# 0-WeightSensor.net
KiCad netlist of a schematic drawn in Altium Designer
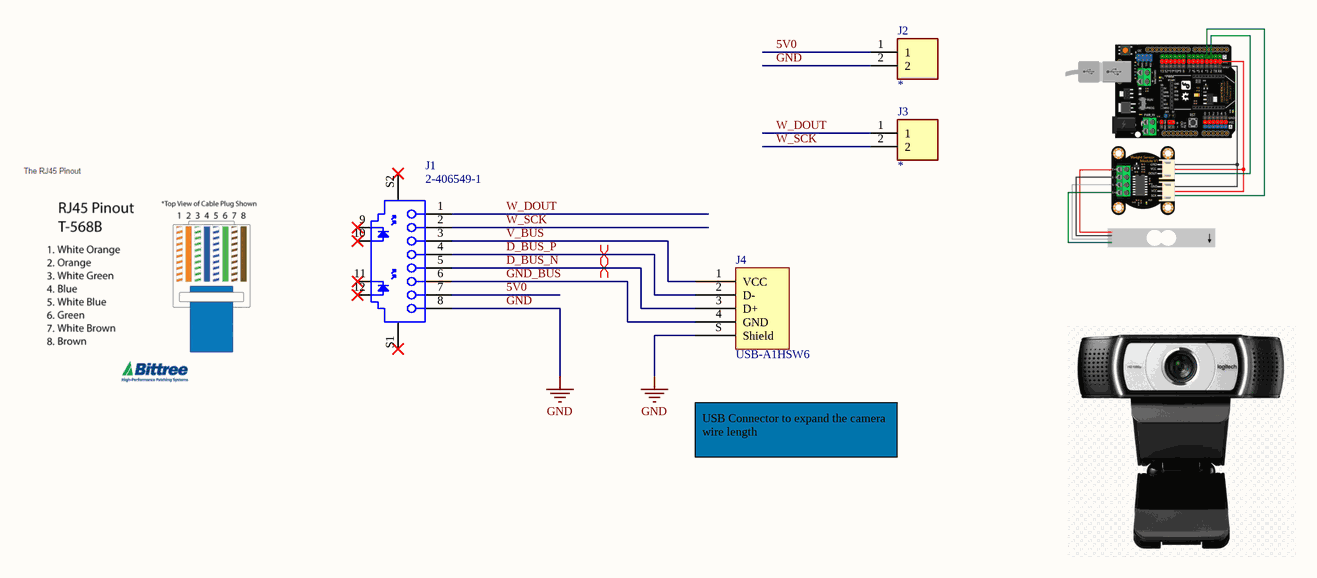
[diagram p0: 0-WeightSensor.SchDoc]

(export (version "E")
  (design (tool "Eeschema 10.0.6"))
  (components
    (comp (ref "J1")
      (value "2-406549-1")
      (footprint "TECO-2-406549-1_V")
      (description "RJ45 Connector, Pitch 1.016 mm, 8 Position, Height 14.22 mm, Tail Length 3.18 mm, RoHS, Tray")
      (fields (field (name "MANUFACTURER") "TE Connectivity"))
      (libsource (lib "Altium Content Vault") (part "RJ45-12-2SHLD_A"))
    )
    (comp (ref "J2")
      (value "282841-2")
      (footprint "TE_282841-2")
      (description "Conn Terminal Block 2 POS 5.08mm Solder ST Thru-Hole 17.5A/Contact")
      (fields (field (name "MF") "TE Connectivity") (field (name "COMMENT_1") "*"))
      (libsource (lib "PTR500-2") (part "282841-2"))
    )
    (comp (ref "J3")
      (value "282841-2")
      (footprint "TE_282841-2")
      (description "Conn Terminal Block 2 POS 5.08mm Solder ST Thru-Hole 17.5A/Contact")
      (fields (field (name "MF") "TE Connectivity") (field (name "COMMENT_1") "*"))
      (libsource (lib "PTR500-2") (part "282841-2"))
    )
    (comp (ref "J4")
      (value "USB-A1HSW6")
      (footprint "ON SHORE TECHNOLOGY USB-A1HSW6")
      (description "CONN RCPT TYPEA 4POS R/A")
      (libsource (lib "Celestial Altium Library - altium_library") (part "USB 2.0 TYPE A"))
    )
  )
  (nets
    (net (code "1") (name "/5V0") (class "Default")
      (node (ref "J1") (pin "7") (pinfunction "7_7") (pintype "passive"))
      (node (ref "J2") (pin "1") (pinfunction "1_1") (pintype "passive"))
    )
    (net (code "2") (name "/D_BUS_N") (class "Default")
      (node (ref "J1") (pin "5") (pinfunction "5_5") (pintype "passive"))
      (node (ref "J4") (pin "3") (pinfunction "D+_3") (pintype "passive"))
    )
    (net (code "3") (name "/D_BUS_P") (class "Default")
      (node (ref "J1") (pin "4") (pinfunction "4_4") (pintype "passive"))
      (node (ref "J4") (pin "2") (pinfunction "D-_2") (pintype "passive"))
    )
    (net (code "4") (name "/GND_BUS") (class "Default")
      (node (ref "J1") (pin "6") (pinfunction "6_6") (pintype "passive"))
      (node (ref "J4") (pin "4") (pinfunction "GND_4") (pintype "passive"))
    )
    (net (code "5") (name "/V_BUS") (class "Default")
      (node (ref "J1") (pin "3") (pinfunction "3_3") (pintype "passive"))
      (node (ref "J4") (pin "1") (pinfunction "VCC_1") (pintype "passive"))
    )
    (net (code "6") (name "/W_DOUT") (class "Default")
      (node (ref "J1") (pin "1") (pinfunction "1_1") (pintype "passive"))
      (node (ref "J3") (pin "1") (pinfunction "1_1") (pintype "passive"))
    )
    (net (code "7") (name "/W_SCK") (class "Default")
      (node (ref "J1") (pin "2") (pinfunction "2_2") (pintype "passive"))
      (node (ref "J3") (pin "2") (pinfunction "2_2") (pintype "passive"))
    )
    (net (code "8") (name "GND") (class "Default")
      (node (ref "J1") (pin "8") (pinfunction "8_8") (pintype "passive"))
      (node (ref "J2") (pin "2") (pinfunction "2_2") (pintype "passive"))
      (node (ref "J4") (pin "S") (pinfunction "Shield_S") (pintype "passive"))
    )
    (net (code "9") (name "unconnected-(J1-Pad9)") (class "Default")
      (node (ref "J1") (pin "9") (pinfunction "9_9") (pintype "passive+no_connect"))
    )
    (net (code "10") (name "unconnected-(J1-Pad10)") (class "Default")
      (node (ref "J1") (pin "10") (pinfunction "10_10") (pintype "passive+no_connect"))
    )
    (net (code "11") (name "unconnected-(J1-Pad11)") (class "Default")
      (node (ref "J1") (pin "11") (pinfunction "11_11") (pintype "passive+no_connect"))
    )
    (net (code "12") (name "unconnected-(J1-Pad12)") (class "Default")
      (node (ref "J1") (pin "12") (pinfunction "12_12") (pintype "passive+no_connect"))
    )
    (net (code "13") (name "unconnected-(J1-PadS1)") (class "Default")
      (node (ref "J1") (pin "S1") (pinfunction "S1_S1") (pintype "passive+no_connect"))
    )
    (net (code "14") (name "unconnected-(J1-PadS2)") (class "Default")
      (node (ref "J1") (pin "S2") (pinfunction "S2_S2") (pintype "passive+no_connect"))
    )
  )
)
